# dissolutionShield.net
KiCad netlist of a schematic drawn in EAGLE
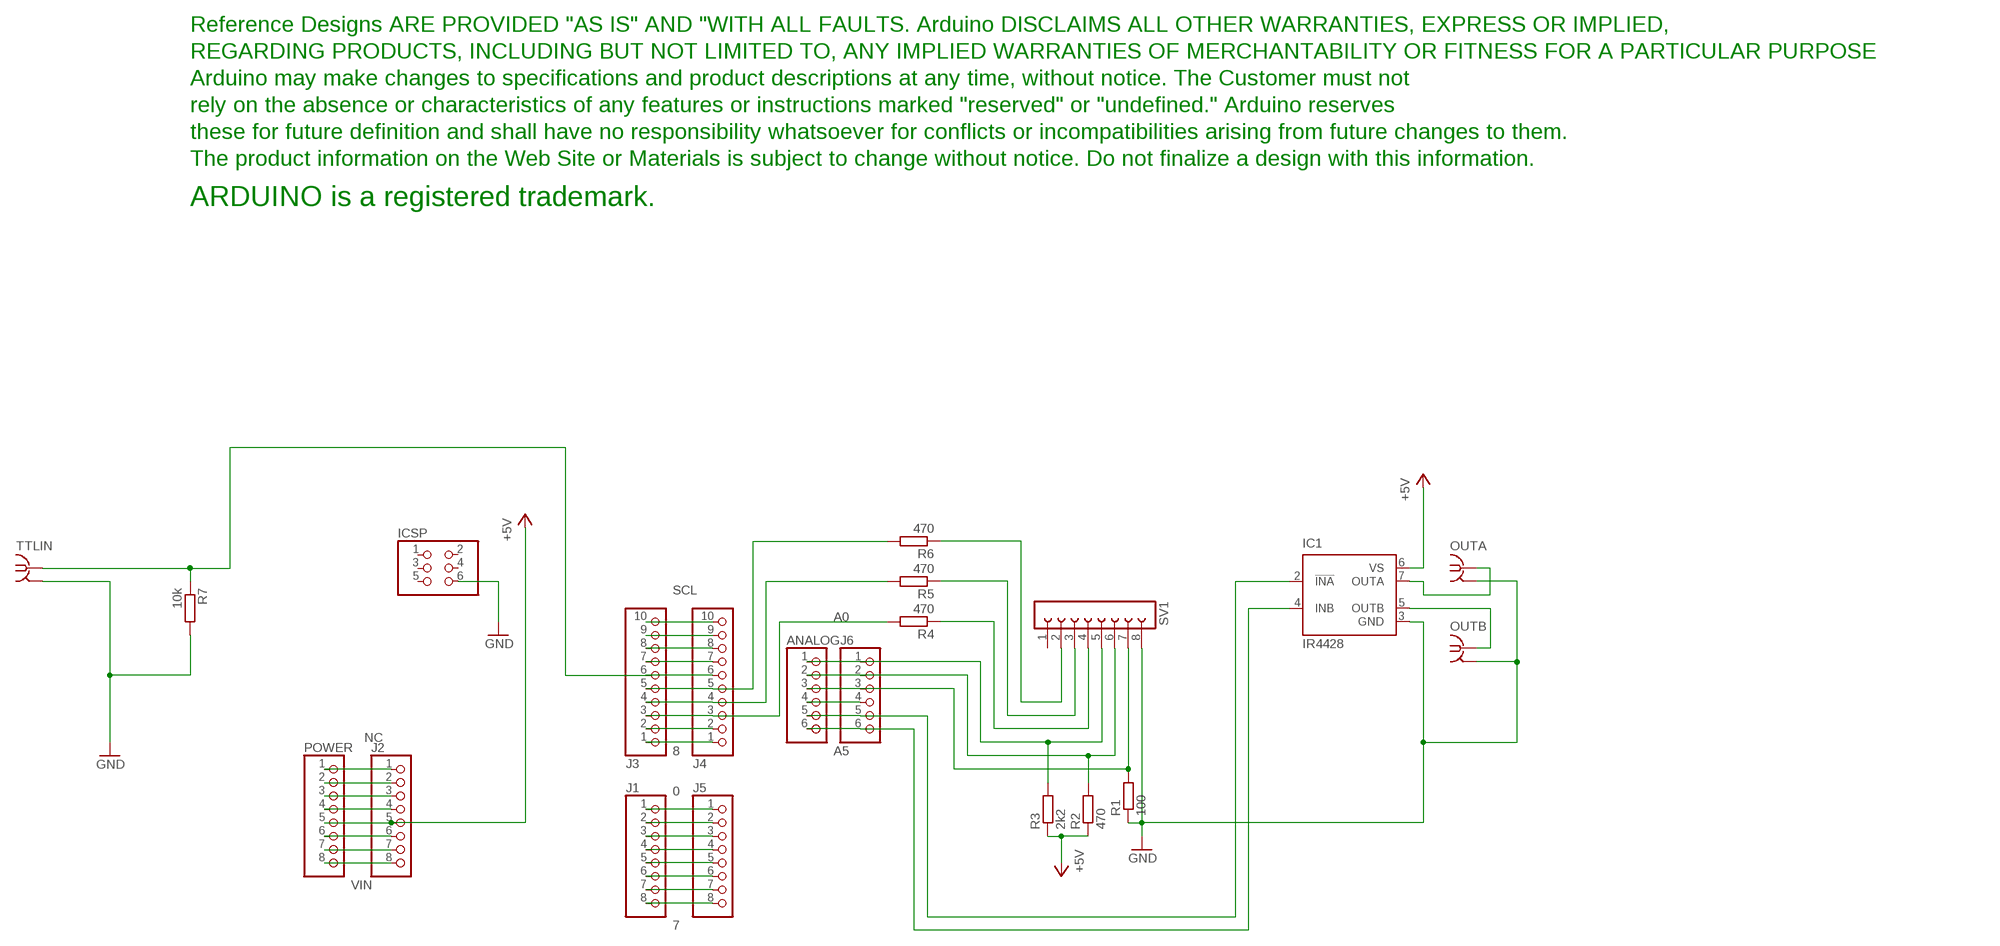
[diagram p0: schematic, sheet 1]

(export (version "E")
  (design (tool "Eeschema 10.0.6"))
  (components
    (comp (ref "ANALOG")
      (value "PINHD-1X6")
      (footprint "eagle-import:1X06")
      (libsource (lib "eagle-import") (part "PINHD-1X6"))
    )
    (comp (ref "IC1")
      (value "IR4428")
      (footprint "eagle-import:DIL08")
      (fields (field (name "MF") "INTERNATIONAL RECTIFIER(IR)") (field (name "MPN") "IR4428PBF"))
      (libsource (lib "eagle-import") (part "IR4428"))
    )
    (comp (ref "ICSP")
      (value "PINHD-2X3")
      (footprint "eagle-import:2X03")
      (libsource (lib "eagle-import") (part "PINHD-2X3"))
    )
    (comp (ref "J1")
      (value "PINHD-1X8TH")
      (footprint "eagle-import:1X08-TH")
      (libsource (lib "eagle-import") (part "PINHD-1X8TH"))
    )
    (comp (ref "J2")
      (value "PINHD-1X8TH")
      (footprint "eagle-import:1X08-TH")
      (libsource (lib "eagle-import") (part "PINHD-1X8TH"))
    )
    (comp (ref "J3")
      (value "PINHD-1X10TH")
      (footprint "eagle-import:1X10-TH")
      (libsource (lib "eagle-import") (part "PINHD-1X10TH"))
    )
    (comp (ref "J4")
      (value "PINHD-1X10TH")
      (footprint "eagle-import:1X10-TH")
      (libsource (lib "eagle-import") (part "PINHD-1X10TH"))
    )
    (comp (ref "J5")
      (value "PINHD-1X8TH")
      (footprint "eagle-import:1X08-TH")
      (libsource (lib "eagle-import") (part "PINHD-1X8TH"))
    )
    (comp (ref "J6")
      (value "PINHD-1X6")
      (footprint "eagle-import:1X06")
      (libsource (lib "eagle-import") (part "PINHD-1X6"))
    )
    (comp (ref "OUTA")
      (value "BU-SMA-H")
      (footprint "eagle-import:BU-SMA-H")
      (libsource (lib "eagle-import") (part "BU-SMA-H"))
    )
    (comp (ref "OUTB")
      (value "BU-SMA-H")
      (footprint "eagle-import:BU-SMA-H")
      (libsource (lib "eagle-import") (part "BU-SMA-H"))
    )
    (comp (ref "POWER")
      (value "PINHD-1X8TH")
      (footprint "eagle-import:1X08-TH")
      (libsource (lib "eagle-import") (part "PINHD-1X8TH"))
    )
    (comp (ref "R1")
      (value "100")
      (footprint "eagle-import:0207_10")
      (libsource (lib "eagle-import") (part "R-EU_0207/10"))
    )
    (comp (ref "R2")
      (value "470")
      (footprint "eagle-import:0207_10")
      (libsource (lib "eagle-import") (part "R-EU_0207/10"))
    )
    (comp (ref "R3")
      (value "2k2")
      (footprint "eagle-import:0207_10")
      (libsource (lib "eagle-import") (part "R-EU_0207/10"))
    )
    (comp (ref "R4")
      (value "470")
      (footprint "eagle-import:0207_10")
      (libsource (lib "eagle-import") (part "R-EU_0207/10"))
    )
    (comp (ref "R5")
      (value "470")
      (footprint "eagle-import:0207_10")
      (libsource (lib "eagle-import") (part "R-EU_0207/10"))
    )
    (comp (ref "R6")
      (value "470")
      (footprint "eagle-import:0207_10")
      (libsource (lib "eagle-import") (part "R-EU_0207/10"))
    )
    (comp (ref "R7")
      (value "10k")
      (footprint "eagle-import:0207_10")
      (libsource (lib "eagle-import") (part "R-EU_0207/10"))
    )
    (comp (ref "SV1")
      (value "FE08-1")
      (footprint "eagle-import:FE08")
      (libsource (lib "eagle-import") (part "FE08-1"))
    )
    (comp (ref "TTLIN")
      (value "BU-SMA-H")
      (footprint "eagle-import:BU-SMA-H")
      (libsource (lib "eagle-import") (part "BU-SMA-H"))
    )
    (comp (ref "U$1")
      (value "DISCLAIMER")
      (footprint "eagle-import:DISCLAIMER")
      (libsource (lib "eagle-import") (part "DISCLAIMER"))
    )
  )
  (nets
    (net (code "1") (name "+5V") (class "Default")
      (node (ref "IC1") (pin "6") (pinfunction "VS_6") (pintype "power_in"))
      (node (ref "J2") (pin "5") (pinfunction "5_5") (pintype "passive"))
      (node (ref "POWER") (pin "5") (pinfunction "5_5") (pintype "passive"))
      (node (ref "R2") (pin "1") (pinfunction "1_1") (pintype "passive"))
      (node (ref "R3") (pin "1") (pinfunction "1_1") (pintype "passive"))
    )
    (net (code "2") (name "/0") (class "Default")
      (node (ref "J1") (pin "1") (pinfunction "1_1") (pintype "passive"))
      (node (ref "J5") (pin "1") (pinfunction "1_1") (pintype "passive"))
    )
    (net (code "3") (name "/7") (class "Default")
      (node (ref "J1") (pin "8") (pinfunction "8_8") (pintype "passive"))
      (node (ref "J5") (pin "8") (pinfunction "8_8") (pintype "passive"))
    )
    (net (code "4") (name "/8") (class "Default")
      (node (ref "J3") (pin "1") (pinfunction "1_1") (pintype "passive"))
      (node (ref "J4") (pin "1") (pinfunction "1_1") (pintype "passive"))
    )
    (net (code "5") (name "/A0") (class "Default")
      (node (ref "ANALOG") (pin "1") (pinfunction "1_1") (pintype "passive"))
      (node (ref "J6") (pin "1") (pinfunction "1_1") (pintype "passive"))
      (node (ref "R3") (pin "2") (pinfunction "2_2") (pintype "passive"))
      (node (ref "SV1") (pin "5") (pinfunction "5_5") (pintype "passive"))
    )
    (net (code "6") (name "/A5") (class "Default")
      (node (ref "ANALOG") (pin "6") (pinfunction "6_6") (pintype "passive"))
      (node (ref "IC1") (pin "4") (pinfunction "INB_4") (pintype "input"))
      (node (ref "J6") (pin "6") (pinfunction "6_6") (pintype "passive"))
    )
    (net (code "7") (name "/NC") (class "Default")
      (node (ref "J2") (pin "1") (pinfunction "1_1") (pintype "passive"))
      (node (ref "POWER") (pin "1") (pinfunction "1_1") (pintype "passive"))
    )
    (net (code "8") (name "/SCL") (class "Default")
      (node (ref "J3") (pin "10") (pinfunction "10_10") (pintype "passive"))
      (node (ref "J4") (pin "10") (pinfunction "10_10") (pintype "passive"))
    )
    (net (code "9") (name "/VIN") (class "Default")
      (node (ref "J2") (pin "8") (pinfunction "8_8") (pintype "passive"))
      (node (ref "POWER") (pin "8") (pinfunction "8_8") (pintype "passive"))
    )
    (net (code "10") (name "GND") (class "Default")
      (node (ref "IC1") (pin "3") (pinfunction "GND_3") (pintype "power_in"))
      (node (ref "ICSP") (pin "6") (pinfunction "6_6") (pintype "passive"))
      (node (ref "J2") (pin "6") (pinfunction "6_6") (pintype "passive"))
      (node (ref "J2") (pin "7") (pinfunction "7_7") (pintype "passive"))
      (node (ref "J3") (pin "7") (pinfunction "7_7") (pintype "passive"))
      (node (ref "J4") (pin "7") (pinfunction "7_7") (pintype "passive"))
      (node (ref "OUTA") (pin "2") (pinfunction "2_2") (pintype "passive"))
      (node (ref "OUTA") (pin "3") (pinfunction "2_3") (pintype "passive"))
      (node (ref "OUTA") (pin "4") (pinfunction "2_4") (pintype "passive"))
      (node (ref "OUTA") (pin "5") (pinfunction "2_5") (pintype "passive"))
      (node (ref "OUTB") (pin "2") (pinfunction "2_2") (pintype "passive"))
      (node (ref "OUTB") (pin "3") (pinfunction "2_3") (pintype "passive"))
      (node (ref "OUTB") (pin "4") (pinfunction "2_4") (pintype "passive"))
      (node (ref "OUTB") (pin "5") (pinfunction "2_5") (pintype "passive"))
      (node (ref "POWER") (pin "6") (pinfunction "6_6") (pintype "passive"))
      (node (ref "POWER") (pin "7") (pinfunction "7_7") (pintype "passive"))
      (node (ref "R1") (pin "1") (pinfunction "1_1") (pintype "passive"))
      (node (ref "R7") (pin "2") (pinfunction "2_2") (pintype "passive"))
      (node (ref "SV1") (pin "8") (pinfunction "8_8") (pintype "passive"))
      (node (ref "TTLIN") (pin "2") (pinfunction "2_2") (pintype "passive"))
      (node (ref "TTLIN") (pin "3") (pinfunction "2_3") (pintype "passive"))
      (node (ref "TTLIN") (pin "4") (pinfunction "2_4") (pintype "passive"))
      (node (ref "TTLIN") (pin "5") (pinfunction "2_5") (pintype "passive"))
    )
    (net (code "11") (name "Net-(ANALOG-Pad2)") (class "Default")
      (node (ref "ANALOG") (pin "2") (pinfunction "2_2") (pintype "passive"))
      (node (ref "J6") (pin "2") (pinfunction "2_2") (pintype "passive"))
      (node (ref "R2") (pin "2") (pinfunction "2_2") (pintype "passive"))
      (node (ref "SV1") (pin "6") (pinfunction "6_6") (pintype "passive"))
    )
    (net (code "12") (name "Net-(ANALOG-Pad3)") (class "Default")
      (node (ref "ANALOG") (pin "3") (pinfunction "3_3") (pintype "passive"))
      (node (ref "J6") (pin "3") (pinfunction "3_3") (pintype "passive"))
      (node (ref "R1") (pin "2") (pinfunction "2_2") (pintype "passive"))
      (node (ref "SV1") (pin "7") (pinfunction "7_7") (pintype "passive"))
    )
    (net (code "13") (name "Net-(ANALOG-Pad4)") (class "Default")
      (node (ref "ANALOG") (pin "4") (pinfunction "4_4") (pintype "passive"))
      (node (ref "J6") (pin "4") (pinfunction "4_4") (pintype "passive"))
    )
    (net (code "14") (name "Net-(IC1-OUTA)") (class "Default")
      (node (ref "IC1") (pin "7") (pinfunction "OUTA_7") (pintype "output"))
      (node (ref "OUTA") (pin "1") (pinfunction "1_1") (pintype "passive"))
    )
    (net (code "15") (name "Net-(IC1-OUTB)") (class "Default")
      (node (ref "IC1") (pin "5") (pinfunction "OUTB_5") (pintype "output"))
      (node (ref "OUTB") (pin "1") (pinfunction "1_1") (pintype "passive"))
    )
    (net (code "16") (name "Net-(IC1-~{INA})") (class "Default")
      (node (ref "ANALOG") (pin "5") (pinfunction "5_5") (pintype "passive"))
      (node (ref "IC1") (pin "2") (pinfunction "~{INA}_2") (pintype "input"))
      (node (ref "J6") (pin "5") (pinfunction "5_5") (pintype "passive"))
    )
    (net (code "17") (name "Net-(J1-Pad2)") (class "Default")
      (node (ref "J1") (pin "2") (pinfunction "2_2") (pintype "passive"))
      (node (ref "J5") (pin "2") (pinfunction "2_2") (pintype "passive"))
    )
    (net (code "18") (name "Net-(J1-Pad3)") (class "Default")
      (node (ref "J1") (pin "3") (pinfunction "3_3") (pintype "passive"))
      (node (ref "J5") (pin "3") (pinfunction "3_3") (pintype "passive"))
    )
    (net (code "19") (name "Net-(J1-Pad4)") (class "Default")
      (node (ref "J1") (pin "4") (pinfunction "4_4") (pintype "passive"))
      (node (ref "J5") (pin "4") (pinfunction "4_4") (pintype "passive"))
    )
    (net (code "20") (name "Net-(J1-Pad5)") (class "Default")
      (node (ref "J1") (pin "5") (pinfunction "5_5") (pintype "passive"))
      (node (ref "J5") (pin "5") (pinfunction "5_5") (pintype "passive"))
    )
    (net (code "21") (name "Net-(J1-Pad6)") (class "Default")
      (node (ref "J1") (pin "6") (pinfunction "6_6") (pintype "passive"))
      (node (ref "J5") (pin "6") (pinfunction "6_6") (pintype "passive"))
    )
    (net (code "22") (name "Net-(J1-Pad7)") (class "Default")
      (node (ref "J1") (pin "7") (pinfunction "7_7") (pintype "passive"))
      (node (ref "J5") (pin "7") (pinfunction "7_7") (pintype "passive"))
    )
    (net (code "23") (name "Net-(J2-Pad2)") (class "Default")
      (node (ref "J2") (pin "2") (pinfunction "2_2") (pintype "passive"))
      (node (ref "POWER") (pin "2") (pinfunction "2_2") (pintype "passive"))
    )
    (net (code "24") (name "Net-(J2-Pad3)") (class "Default")
      (node (ref "J2") (pin "3") (pinfunction "3_3") (pintype "passive"))
      (node (ref "POWER") (pin "3") (pinfunction "3_3") (pintype "passive"))
    )
    (net (code "25") (name "Net-(J2-Pad4)") (class "Default")
      (node (ref "J2") (pin "4") (pinfunction "4_4") (pintype "passive"))
      (node (ref "POWER") (pin "4") (pinfunction "4_4") (pintype "passive"))
    )
    (net (code "26") (name "Net-(J3-Pad2)") (class "Default")
      (node (ref "J3") (pin "2") (pinfunction "2_2") (pintype "passive"))
      (node (ref "J4") (pin "2") (pinfunction "2_2") (pintype "passive"))
    )
    (net (code "27") (name "Net-(J3-Pad3)") (class "Default")
      (node (ref "J3") (pin "3") (pinfunction "3_3") (pintype "passive"))
      (node (ref "J4") (pin "3") (pinfunction "3_3") (pintype "passive"))
      (node (ref "R4") (pin "2") (pinfunction "2_2") (pintype "passive"))
    )
    (net (code "28") (name "Net-(J3-Pad4)") (class "Default")
      (node (ref "J3") (pin "4") (pinfunction "4_4") (pintype "passive"))
      (node (ref "J4") (pin "4") (pinfunction "4_4") (pintype "passive"))
      (node (ref "R5") (pin "2") (pinfunction "2_2") (pintype "passive"))
    )
    (net (code "29") (name "Net-(J3-Pad5)") (class "Default")
      (node (ref "J3") (pin "5") (pinfunction "5_5") (pintype "passive"))
      (node (ref "J4") (pin "5") (pinfunction "5_5") (pintype "passive"))
      (node (ref "R6") (pin "2") (pinfunction "2_2") (pintype "passive"))
    )
    (net (code "30") (name "Net-(J3-Pad6)") (class "Default")
      (node (ref "J3") (pin "6") (pinfunction "6_6") (pintype "passive"))
      (node (ref "J4") (pin "6") (pinfunction "6_6") (pintype "passive"))
      (node (ref "R7") (pin "1") (pinfunction "1_1") (pintype "passive"))
      (node (ref "TTLIN") (pin "1") (pinfunction "1_1") (pintype "passive"))
    )
    (net (code "31") (name "Net-(J3-Pad8)") (class "Default")
      (node (ref "J3") (pin "8") (pinfunction "8_8") (pintype "passive"))
      (node (ref "J4") (pin "8") (pinfunction "8_8") (pintype "passive"))
    )
    (net (code "32") (name "Net-(J3-Pad9)") (class "Default")
      (node (ref "J3") (pin "9") (pinfunction "9_9") (pintype "passive"))
      (node (ref "J4") (pin "9") (pinfunction "9_9") (pintype "passive"))
    )
    (net (code "33") (name "Net-(R4-Pad1)") (class "Default")
      (node (ref "R4") (pin "1") (pinfunction "1_1") (pintype "passive"))
      (node (ref "SV1") (pin "4") (pinfunction "4_4") (pintype "passive"))
    )
    (net (code "34") (name "Net-(R5-Pad1)") (class "Default")
      (node (ref "R5") (pin "1") (pinfunction "1_1") (pintype "passive"))
      (node (ref "SV1") (pin "3") (pinfunction "3_3") (pintype "passive"))
    )
    (net (code "35") (name "Net-(R6-Pad1)") (class "Default")
      (node (ref "R6") (pin "1") (pinfunction "1_1") (pintype "passive"))
      (node (ref "SV1") (pin "2") (pinfunction "2_2") (pintype "passive"))
    )
    (net (code "36") (name "unconnected-(ICSP-Pad1)") (class "Default")
      (node (ref "ICSP") (pin "1") (pinfunction "1_1") (pintype "passive"))
    )
    (net (code "37") (name "unconnected-(ICSP-Pad2)") (class "Default")
      (node (ref "ICSP") (pin "2") (pinfunction "2_2") (pintype "passive"))
    )
    (net (code "38") (name "unconnected-(ICSP-Pad3)") (class "Default")
      (node (ref "ICSP") (pin "3") (pinfunction "3_3") (pintype "passive"))
    )
    (net (code "39") (name "unconnected-(ICSP-Pad4)") (class "Default")
      (node (ref "ICSP") (pin "4") (pinfunction "4_4") (pintype "passive"))
    )
    (net (code "40") (name "unconnected-(ICSP-Pad5)") (class "Default")
      (node (ref "ICSP") (pin "5") (pinfunction "5_5") (pintype "passive"))
    )
    (net (code "41") (name "unconnected-(SV1-Pad1)") (class "Default")
      (node (ref "SV1") (pin "1") (pinfunction "1_1") (pintype "passive"))
    )
  )
)
